# AndrewSaLoutos_pcb.net
KiCad netlist of a schematic drawn in EAGLE
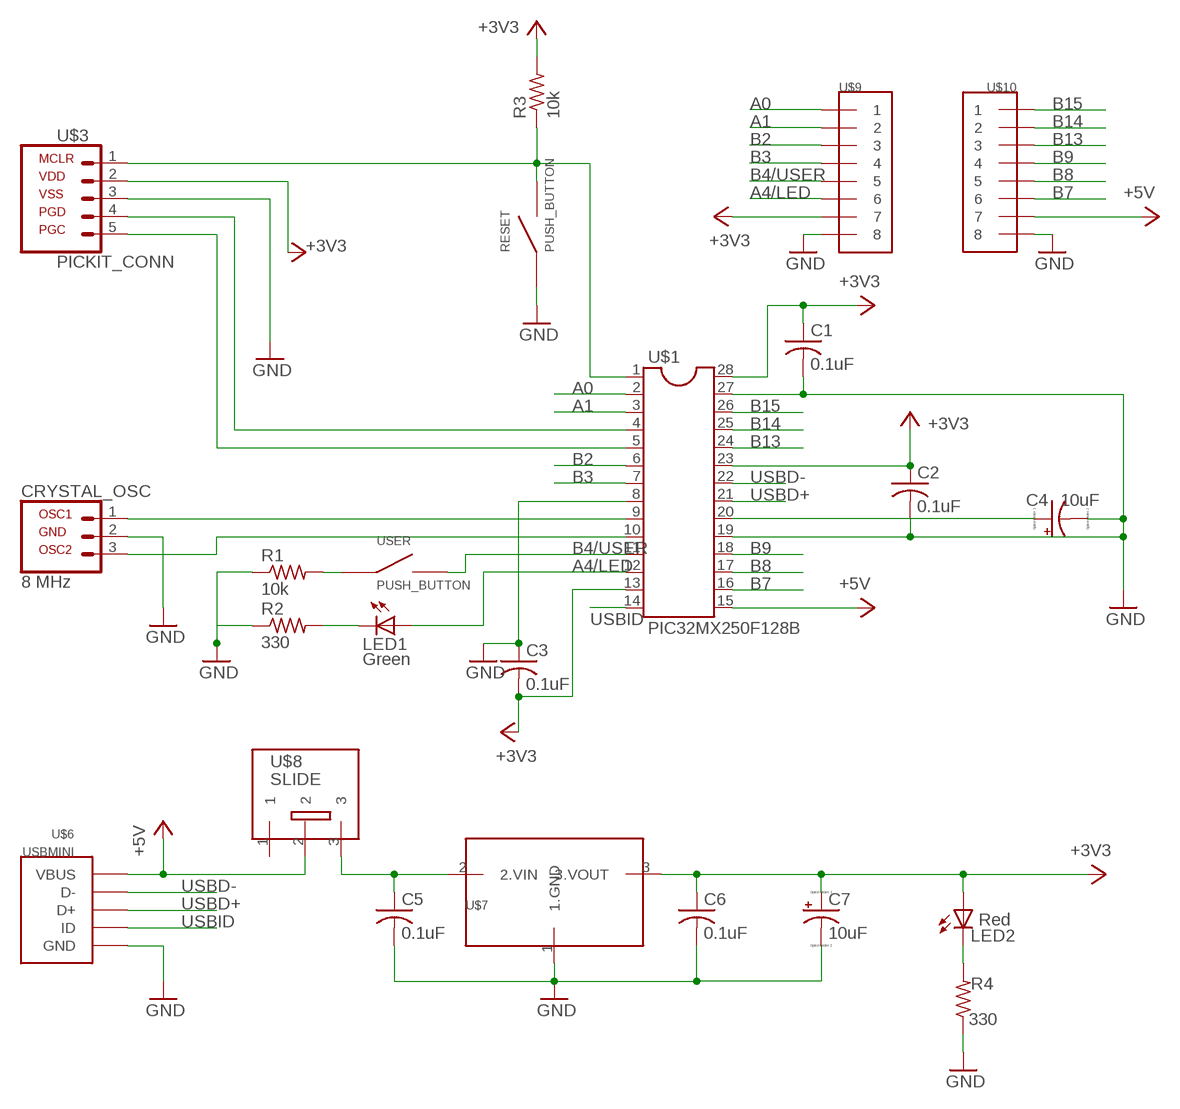
[diagram p0: schematic, sheet 1]

(export (version "E")
  (design (tool "Eeschema 10.0.6"))
  (components
    (comp (ref "C1")
      (value "0.1uF")
      (footprint "eagle-import:C050-030X075")
      (libsource (lib "eagle-import") (part "C-US050-030X075"))
    )
    (comp (ref "C2")
      (value "0.1uF")
      (footprint "eagle-import:C050-030X075")
      (libsource (lib "eagle-import") (part "C-US050-030X075"))
    )
    (comp (ref "C3")
      (value "0.1uF")
      (footprint "eagle-import:C050-030X075")
      (libsource (lib "eagle-import") (part "C-US050-030X075"))
    )
    (comp (ref "C4")
      (value "10uF")
      (footprint "eagle-import:E2,5-6")
      (libsource (lib "eagle-import") (part "CPOL-USE2.5-6"))
    )
    (comp (ref "C5")
      (value "0.1uF")
      (footprint "eagle-import:C050-030X075")
      (libsource (lib "eagle-import") (part "C-US050-030X075"))
    )
    (comp (ref "C6")
      (value "0.1uF")
      (footprint "eagle-import:C050-030X075")
      (libsource (lib "eagle-import") (part "C-US050-030X075"))
    )
    (comp (ref "C7")
      (value "10uF")
      (footprint "eagle-import:E2,5-6")
      (libsource (lib "eagle-import") (part "CPOL-USE2.5-6"))
    )
    (comp (ref "CRYSTAL_OSC")
      (value "8 MHz")
      (footprint "eagle-import:1X03")
      (libsource (lib "eagle-import") (part "CRYSTAL_OSC"))
    )
    (comp (ref "LED1")
      (value "Green")
      (footprint "eagle-import:LED3MM")
      (libsource (lib "eagle-import") (part "LED3MM"))
    )
    (comp (ref "LED2")
      (value "Red")
      (footprint "eagle-import:LED3MM")
      (libsource (lib "eagle-import") (part "LED3MM"))
    )
    (comp (ref "R1")
      (value "10k")
      (footprint "eagle-import:0207_10")
      (libsource (lib "eagle-import") (part "R-US_0207/10"))
    )
    (comp (ref "R2")
      (value "330")
      (footprint "eagle-import:0207_10")
      (libsource (lib "eagle-import") (part "R-US_0207/10"))
    )
    (comp (ref "R3")
      (value "10k")
      (footprint "eagle-import:0207_10")
      (libsource (lib "eagle-import") (part "R-US_0207/10"))
    )
    (comp (ref "R4")
      (value "330")
      (footprint "eagle-import:0207_10")
      (libsource (lib "eagle-import") (part "R-US_0207/10"))
    )
    (comp (ref "RESET")
      (value "PUSH_BUTTON")
      (footprint "eagle-import:PUSH_BUTTON")
      (libsource (lib "eagle-import") (part "PUSH_BUTTON"))
    )
    (comp (ref "U$1")
      (value "PIC32MX250F128B")
      (footprint "eagle-import:DIL28-3")
      (libsource (lib "eagle-import") (part "PIC32MX250F128B"))
    )
    (comp (ref "U$3")
      (value "PICKIT_CONN")
      (footprint "eagle-import:1X05")
      (libsource (lib "eagle-import") (part "PICKIT_CONN"))
    )
    (comp (ref "U$6")
      (value "USBMINI")
      (footprint "eagle-import:USB-MB-H")
      (libsource (lib "eagle-import") (part "USBMINI_GOOD"))
    )
    (comp (ref "U$7")
      (value "MCP1702")
      (footprint "eagle-import:TO92")
      (libsource (lib "eagle-import") (part "MCP1702"))
    )
    (comp (ref "U$8")
      (value "SLIDE")
      (footprint "eagle-import:SLIDE")
      (libsource (lib "eagle-import") (part "SLIDE"))
    )
    (comp (ref "U$9")
      (value "8PIN_HEADER")
      (footprint "eagle-import:8PIN_HEADER")
      (libsource (lib "eagle-import") (part "8PIN_HEADER"))
    )
    (comp (ref "U$10")
      (value "8PIN_HEADER")
      (footprint "eagle-import:8PIN_HEADER")
      (libsource (lib "eagle-import") (part "8PIN_HEADER"))
    )
    (comp (ref "USER")
      (value "PUSH_BUTTON")
      (footprint "eagle-import:PUSH_BUTTON")
      (libsource (lib "eagle-import") (part "PUSH_BUTTON"))
    )
  )
  (nets
    (net (code "1") (name "+3V3") (class "Default")
      (node (ref "C1") (pin "1") (pinfunction "1_1") (pintype "passive"))
      (node (ref "C2") (pin "1") (pinfunction "1_1") (pintype "passive"))
      (node (ref "C3") (pin "2") (pinfunction "2_2") (pintype "passive"))
      (node (ref "C6") (pin "1") (pinfunction "1_1") (pintype "passive"))
      (node (ref "C7") (pin "+") (pinfunction "+_+") (pintype "passive"))
      (node (ref "LED2") (pin "A") (pinfunction "A_A") (pintype "passive"))
      (node (ref "R3") (pin "2") (pinfunction "2_2") (pintype "passive"))
      (node (ref "U$1") (pin "13") (pinfunction "13.VDD_13") (pintype "passive"))
      (node (ref "U$1") (pin "23") (pinfunction "23.VUSB3.3_23") (pintype "passive"))
      (node (ref "U$1") (pin "28") (pinfunction "28.AVDD_28") (pintype "passive"))
      (node (ref "U$3") (pin "2") (pinfunction "2.VDD_2") (pintype "passive"))
      (node (ref "U$7") (pin "3") (pinfunction "3.VOUT_3") (pintype "bidirectional"))
      (node (ref "U$9") (pin "7") (pinfunction "7_7") (pintype "bidirectional"))
    )
    (net (code "2") (name "+5V") (class "Default")
      (node (ref "U$1") (pin "15") (pinfunction "15.VBUS_15") (pintype "passive"))
      (node (ref "U$10") (pin "7") (pinfunction "7_7") (pintype "bidirectional"))
      (node (ref "U$6") (pin "VBUS") (pinfunction "VBUS_VBUS") (pintype "bidirectional"))
      (node (ref "U$8") (pin "2") (pinfunction "2_2") (pintype "bidirectional"))
    )
    (net (code "3") (name "/A0") (class "Default")
      (node (ref "U$1") (pin "2") (pinfunction "2_2") (pintype "passive"))
      (node (ref "U$9") (pin "1") (pinfunction "1_1") (pintype "bidirectional"))
    )
    (net (code "4") (name "/A1") (class "Default")
      (node (ref "U$1") (pin "3") (pinfunction "3_3") (pintype "passive"))
      (node (ref "U$9") (pin "2") (pinfunction "2_2") (pintype "bidirectional"))
    )
    (net (code "5") (name "/A4{slash}LED") (class "Default")
      (node (ref "LED1") (pin "A") (pinfunction "A_A") (pintype "passive"))
      (node (ref "U$1") (pin "12") (pinfunction "12.RA4_12") (pintype "passive"))
      (node (ref "U$9") (pin "6") (pinfunction "6_6") (pintype "bidirectional"))
    )
    (net (code "6") (name "/B2") (class "Default")
      (node (ref "U$1") (pin "6") (pinfunction "6_6") (pintype "passive"))
      (node (ref "U$9") (pin "3") (pinfunction "3_3") (pintype "bidirectional"))
    )
    (net (code "7") (name "/B3") (class "Default")
      (node (ref "U$1") (pin "7") (pinfunction "7_7") (pintype "passive"))
      (node (ref "U$9") (pin "4") (pinfunction "4_4") (pintype "bidirectional"))
    )
    (net (code "8") (name "/B4{slash}USER") (class "Default")
      (node (ref "U$1") (pin "11") (pinfunction "11.RB4_11") (pintype "passive"))
      (node (ref "U$9") (pin "5") (pinfunction "5_5") (pintype "bidirectional"))
      (node (ref "USER") (pin "3") (pinfunction "OUT_3") (pintype "bidirectional"))
    )
    (net (code "9") (name "/B7") (class "Default")
      (node (ref "U$1") (pin "16") (pinfunction "16_16") (pintype "passive"))
      (node (ref "U$10") (pin "6") (pinfunction "6_6") (pintype "bidirectional"))
    )
    (net (code "10") (name "/B8") (class "Default")
      (node (ref "U$1") (pin "17") (pinfunction "17_17") (pintype "passive"))
      (node (ref "U$10") (pin "5") (pinfunction "5_5") (pintype "bidirectional"))
    )
    (net (code "11") (name "/B9") (class "Default")
      (node (ref "U$1") (pin "18") (pinfunction "18_18") (pintype "passive"))
      (node (ref "U$10") (pin "4") (pinfunction "4_4") (pintype "bidirectional"))
    )
    (net (code "12") (name "/B13") (class "Default")
      (node (ref "U$1") (pin "24") (pinfunction "24_24") (pintype "passive"))
      (node (ref "U$10") (pin "3") (pinfunction "3_3") (pintype "bidirectional"))
    )
    (net (code "13") (name "/B14") (class "Default")
      (node (ref "U$1") (pin "25") (pinfunction "25_25") (pintype "passive"))
      (node (ref "U$10") (pin "2") (pinfunction "2_2") (pintype "bidirectional"))
    )
    (net (code "14") (name "/B15") (class "Default")
      (node (ref "U$1") (pin "26") (pinfunction "26_26") (pintype "passive"))
      (node (ref "U$10") (pin "1") (pinfunction "1_1") (pintype "bidirectional"))
    )
    (net (code "15") (name "/USBD+") (class "Default")
      (node (ref "U$1") (pin "21") (pinfunction "21_21") (pintype "passive"))
      (node (ref "U$6") (pin "D+") (pinfunction "D+_D+") (pintype "bidirectional"))
    )
    (net (code "16") (name "/USBD-") (class "Default")
      (node (ref "U$1") (pin "22") (pinfunction "22_22") (pintype "passive"))
      (node (ref "U$6") (pin "D-") (pinfunction "D-_D-") (pintype "bidirectional"))
    )
    (net (code "17") (name "/USBID") (class "Default")
      (node (ref "U$1") (pin "14") (pinfunction "14_14") (pintype "passive"))
      (node (ref "U$6") (pin "ID") (pinfunction "ID_ID") (pintype "bidirectional"))
    )
    (net (code "18") (name "GND") (class "Default")
      (node (ref "C1") (pin "2") (pinfunction "2_2") (pintype "passive"))
      (node (ref "C2") (pin "2") (pinfunction "2_2") (pintype "passive"))
      (node (ref "C3") (pin "1") (pinfunction "1_1") (pintype "passive"))
      (node (ref "C4") (pin "-") (pinfunction "-_-") (pintype "passive"))
      (node (ref "C5") (pin "2") (pinfunction "2_2") (pintype "passive"))
      (node (ref "C6") (pin "2") (pinfunction "2_2") (pintype "passive"))
      (node (ref "C7") (pin "-") (pinfunction "-_-") (pintype "passive"))
      (node (ref "CRYSTAL_OSC") (pin "2") (pinfunction "2.GND_2") (pintype "passive"))
      (node (ref "R1") (pin "1") (pinfunction "1_1") (pintype "passive"))
      (node (ref "R2") (pin "1") (pinfunction "1_1") (pintype "passive"))
      (node (ref "R4") (pin "1") (pinfunction "1_1") (pintype "passive"))
      (node (ref "RESET") (pin "1") (pinfunction "IN_1") (pintype "bidirectional"))
      (node (ref "U$1") (pin "19") (pinfunction "19.VSS_19") (pintype "passive"))
      (node (ref "U$1") (pin "27") (pinfunction "27.AVSS_27") (pintype "passive"))
      (node (ref "U$1") (pin "8") (pinfunction "8.VSS_8") (pintype "passive"))
      (node (ref "U$10") (pin "8") (pinfunction "8_8") (pintype "bidirectional"))
      (node (ref "U$3") (pin "3") (pinfunction "3.VSS_3") (pintype "passive"))
      (node (ref "U$6") (pin "GND") (pinfunction "GND_GND") (pintype "bidirectional"))
      (node (ref "U$7") (pin "1") (pinfunction "1.GND_1") (pintype "bidirectional"))
      (node (ref "U$9") (pin "8") (pinfunction "8_8") (pintype "bidirectional"))
    )
    (net (code "19") (name "Net-(CRYSTAL_OSC-1.OSC1)") (class "Default")
      (node (ref "CRYSTAL_OSC") (pin "1") (pinfunction "1.OSC1_1") (pintype "passive"))
      (node (ref "U$1") (pin "9") (pinfunction "9.OSC1_9") (pintype "passive"))
    )
    (net (code "20") (name "Net-(CRYSTAL_OSC-3.OSC2)") (class "Default")
      (node (ref "CRYSTAL_OSC") (pin "3") (pinfunction "3.OSC2_3") (pintype "passive"))
      (node (ref "U$1") (pin "10") (pinfunction "10.OSC2_10") (pintype "passive"))
    )
    (net (code "21") (name "Net-(LED1-C)") (class "Default")
      (node (ref "LED1") (pin "K") (pinfunction "C_K") (pintype "passive"))
      (node (ref "R2") (pin "2") (pinfunction "2_2") (pintype "passive"))
    )
    (net (code "22") (name "Net-(LED2-C)") (class "Default")
      (node (ref "LED2") (pin "K") (pinfunction "C_K") (pintype "passive"))
      (node (ref "R4") (pin "2") (pinfunction "2_2") (pintype "passive"))
    )
    (net (code "23") (name "Net-(RESET-OUT)") (class "Default")
      (node (ref "R3") (pin "1") (pinfunction "1_1") (pintype "passive"))
      (node (ref "RESET") (pin "3") (pinfunction "OUT_3") (pintype "bidirectional"))
      (node (ref "U$1") (pin "1") (pinfunction "1.MCLR_1") (pintype "passive"))
      (node (ref "U$3") (pin "1") (pinfunction "1.MCLR_1") (pintype "passive"))
    )
    (net (code "24") (name "Net-(U$1-4.PGED1)") (class "Default")
      (node (ref "U$1") (pin "4") (pinfunction "4.PGED1_4") (pintype "passive"))
      (node (ref "U$3") (pin "4") (pinfunction "4.PGD_4") (pintype "passive"))
    )
    (net (code "25") (name "Net-(U$1-5.PGEC1)") (class "Default")
      (node (ref "U$1") (pin "5") (pinfunction "5.PGEC1_5") (pintype "passive"))
      (node (ref "U$3") (pin "5") (pinfunction "5.PGC_5") (pintype "passive"))
    )
    (net (code "26") (name "Net-(U$1-20.VCAP)") (class "Default")
      (node (ref "C4") (pin "+") (pinfunction "+_+") (pintype "passive"))
      (node (ref "U$1") (pin "20") (pinfunction "20.VCAP_20") (pintype "passive"))
    )
    (net (code "27") (name "Net-(U$7-2.VIN)") (class "Default")
      (node (ref "C5") (pin "1") (pinfunction "1_1") (pintype "passive"))
      (node (ref "U$7") (pin "2") (pinfunction "2.VIN_2") (pintype "bidirectional"))
      (node (ref "U$8") (pin "3") (pinfunction "3_3") (pintype "bidirectional"))
    )
    (net (code "28") (name "Net-(USER-IN)") (class "Default")
      (node (ref "R1") (pin "2") (pinfunction "2_2") (pintype "passive"))
      (node (ref "USER") (pin "1") (pinfunction "IN_1") (pintype "bidirectional"))
    )
    (net (code "29") (name "unconnected-(U$8-Pad1)") (class "Default")
      (node (ref "U$8") (pin "1") (pinfunction "1_1") (pintype "bidirectional"))
    )
  )
)
